# MCU.net
KiCad netlist of a schematic drawn in Altium Designer
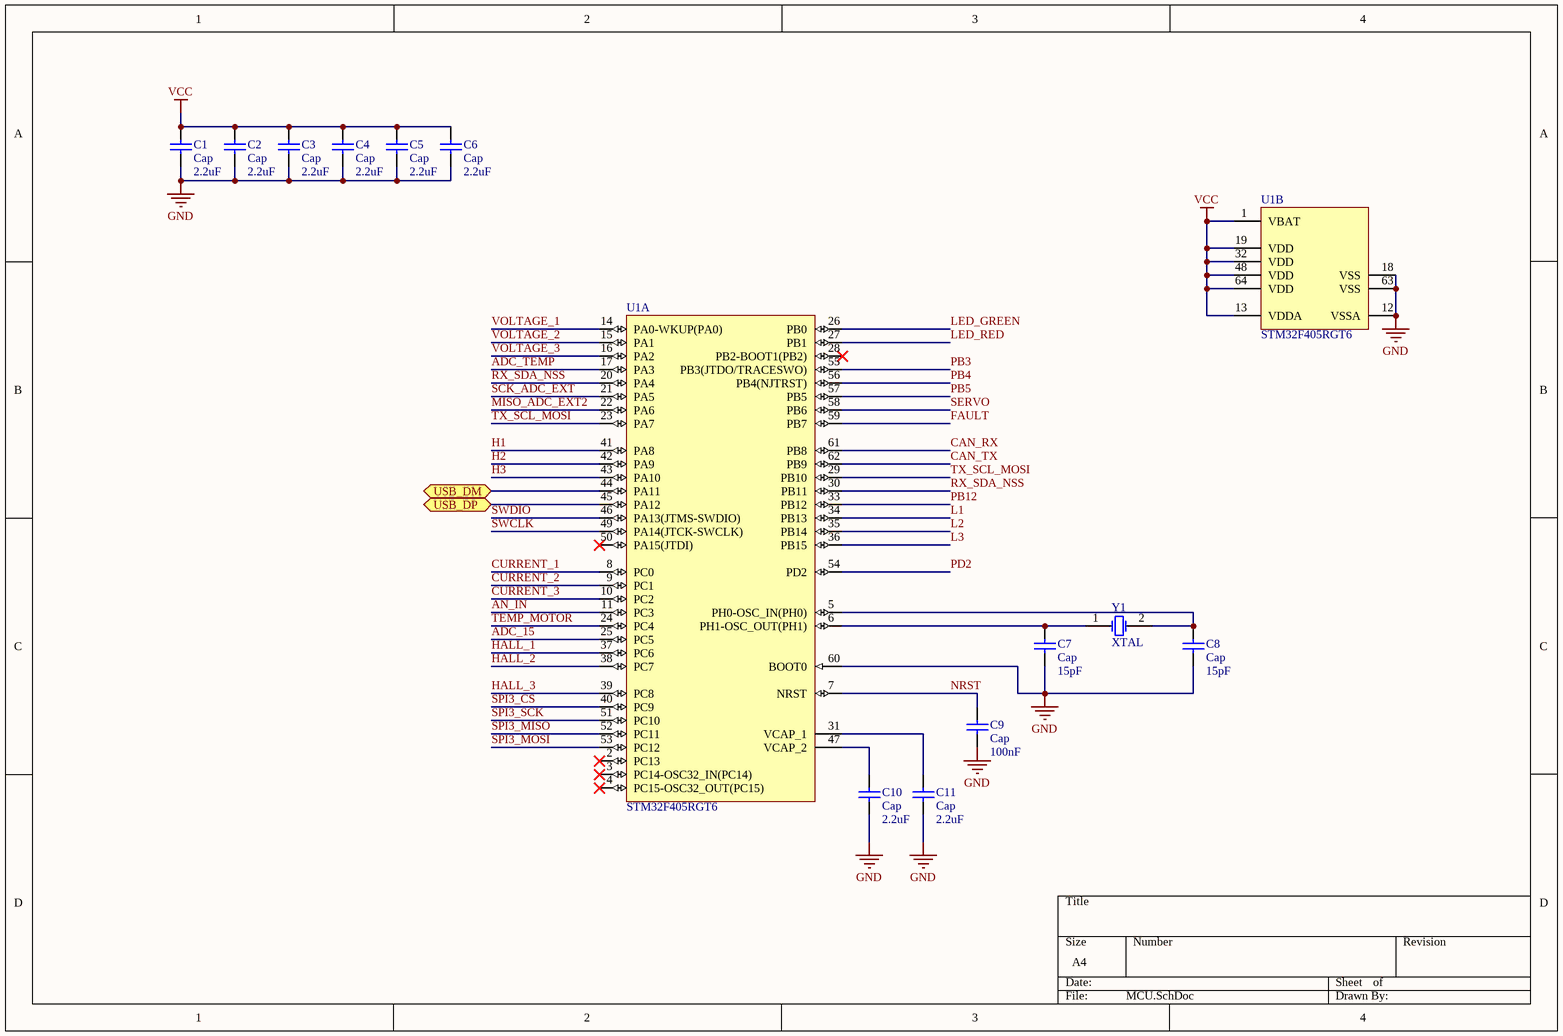
[diagram p0: MCU.SchDoc]

(export (version "E")
  (design (tool "Eeschema 10.0.6"))
  (components
    (comp (ref "C1")
      (value "Cap")
      (footprint "RAD-0.3")
      (description "Capacitor")
      (fields (field (name "ALTIUM_VALUE") "2.2uF") (field (name "PUBLISHER") "Altium Limited"))
      (libsource (lib "Miscellaneous Devices") (part "Cap"))
    )
    (comp (ref "C2")
      (value "Cap")
      (footprint "RAD-0.3")
      (description "Capacitor")
      (fields (field (name "ALTIUM_VALUE") "2.2uF") (field (name "PUBLISHER") "Altium Limited"))
      (libsource (lib "Miscellaneous Devices") (part "Cap"))
    )
    (comp (ref "C3")
      (value "Cap")
      (footprint "RAD-0.3")
      (description "Capacitor")
      (fields (field (name "ALTIUM_VALUE") "2.2uF") (field (name "PUBLISHER") "Altium Limited"))
      (libsource (lib "Miscellaneous Devices") (part "Cap"))
    )
    (comp (ref "C4")
      (value "Cap")
      (footprint "RAD-0.3")
      (description "Capacitor")
      (fields (field (name "ALTIUM_VALUE") "2.2uF") (field (name "PUBLISHER") "Altium Limited"))
      (libsource (lib "Miscellaneous Devices") (part "Cap"))
    )
    (comp (ref "C5")
      (value "Cap")
      (footprint "RAD-0.3")
      (description "Capacitor")
      (fields (field (name "ALTIUM_VALUE") "2.2uF") (field (name "PUBLISHER") "Altium Limited"))
      (libsource (lib "Miscellaneous Devices") (part "Cap"))
    )
    (comp (ref "C6")
      (value "Cap")
      (footprint "RAD-0.3")
      (description "Capacitor")
      (fields (field (name "ALTIUM_VALUE") "2.2uF") (field (name "PUBLISHER") "Altium Limited"))
      (libsource (lib "Miscellaneous Devices") (part "Cap"))
    )
    (comp (ref "C7")
      (value "Cap")
      (footprint "RAD-0.3")
      (description "Capacitor")
      (fields (field (name "ALTIUM_VALUE") "15pF") (field (name "PUBLISHER") "Altium Limited"))
      (libsource (lib "Miscellaneous Devices") (part "Cap"))
    )
    (comp (ref "C8")
      (value "Cap")
      (footprint "RAD-0.3")
      (description "Capacitor")
      (fields (field (name "ALTIUM_VALUE") "15pF") (field (name "PUBLISHER") "Altium Limited"))
      (libsource (lib "Miscellaneous Devices") (part "Cap"))
    )
    (comp (ref "C9")
      (value "Cap")
      (footprint "RAD-0.3")
      (description "Capacitor")
      (fields (field (name "ALTIUM_VALUE") "100nF") (field (name "PUBLISHER") "Altium Limited"))
      (libsource (lib "Miscellaneous Devices") (part "Cap"))
    )
    (comp (ref "C10")
      (value "Cap")
      (footprint "RAD-0.3")
      (description "Capacitor")
      (fields (field (name "ALTIUM_VALUE") "2.2uF") (field (name "PUBLISHER") "Altium Limited"))
      (libsource (lib "Miscellaneous Devices") (part "Cap"))
    )
    (comp (ref "C11")
      (value "Cap")
      (footprint "RAD-0.3")
      (description "Capacitor")
      (fields (field (name "ALTIUM_VALUE") "2.2uF") (field (name "PUBLISHER") "Altium Limited"))
      (libsource (lib "Miscellaneous Devices") (part "Cap"))
    )
    (comp (ref "U1")
      (value "STM32F405RGT6")
      (footprint "STM-LQFP64_M")
      (fields (field (name "MANUFACTURER") "STMicroelectronics"))
      (libsource (lib "Altium Content Vault") (part "MC-ARM-STM32F4X5-SQ64"))
    )
    (comp (ref "Y1")
      (value "XTAL")
      (footprint "R38")
      (description "Crystal Oscillator")
      (fields (field (name "PUBLISHER") "Altium Limited"))
      (libsource (lib "Miscellaneous Devices") (part "XTAL"))
    )
  )
  (nets
    (net (code "1") (name "/ADC_15") (class "Default")
      (node (ref "U1") (pin "25") (pinfunction "PC5_25") (pintype "bidirectional"))
    )
    (net (code "2") (name "/ADC_TEMP") (class "Default")
      (node (ref "U1") (pin "17") (pinfunction "PA3_17") (pintype "bidirectional"))
    )
    (net (code "3") (name "/AN_IN") (class "Default")
      (node (ref "U1") (pin "11") (pinfunction "PC3_11") (pintype "bidirectional"))
    )
    (net (code "4") (name "/CAN_RX") (class "Default")
      (node (ref "U1") (pin "61") (pinfunction "PB8_61") (pintype "bidirectional"))
    )
    (net (code "5") (name "/CAN_TX") (class "Default")
      (node (ref "U1") (pin "62") (pinfunction "PB9_62") (pintype "bidirectional"))
    )
    (net (code "6") (name "/CURRENT_1") (class "Default")
      (node (ref "U1") (pin "8") (pinfunction "PC0_8") (pintype "bidirectional"))
    )
    (net (code "7") (name "/CURRENT_2") (class "Default")
      (node (ref "U1") (pin "9") (pinfunction "PC1_9") (pintype "bidirectional"))
    )
    (net (code "8") (name "/CURRENT_3") (class "Default")
      (node (ref "U1") (pin "10") (pinfunction "PC2_10") (pintype "bidirectional"))
    )
    (net (code "9") (name "/FAULT") (class "Default")
      (node (ref "U1") (pin "59") (pinfunction "PB7_59") (pintype "bidirectional"))
    )
    (net (code "10") (name "/H1") (class "Default")
      (node (ref "U1") (pin "41") (pinfunction "PA8_41") (pintype "bidirectional"))
    )
    (net (code "11") (name "/H2") (class "Default")
      (node (ref "U1") (pin "42") (pinfunction "PA9_42") (pintype "bidirectional"))
    )
    (net (code "12") (name "/H3") (class "Default")
      (node (ref "U1") (pin "43") (pinfunction "PA10_43") (pintype "bidirectional"))
    )
    (net (code "13") (name "/HALL_1") (class "Default")
      (node (ref "U1") (pin "37") (pinfunction "PC6_37") (pintype "bidirectional"))
    )
    (net (code "14") (name "/HALL_2") (class "Default")
      (node (ref "U1") (pin "38") (pinfunction "PC7_38") (pintype "bidirectional"))
    )
    (net (code "15") (name "/HALL_3") (class "Default")
      (node (ref "U1") (pin "39") (pinfunction "PC8_39") (pintype "bidirectional"))
    )
    (net (code "16") (name "/L1") (class "Default")
      (node (ref "U1") (pin "34") (pinfunction "PB13_34") (pintype "bidirectional"))
    )
    (net (code "17") (name "/L2") (class "Default")
      (node (ref "U1") (pin "35") (pinfunction "PB14_35") (pintype "bidirectional"))
    )
    (net (code "18") (name "/L3") (class "Default")
      (node (ref "U1") (pin "36") (pinfunction "PB15_36") (pintype "bidirectional"))
    )
    (net (code "19") (name "/LED_GREEN") (class "Default")
      (node (ref "U1") (pin "26") (pinfunction "PB0_26") (pintype "bidirectional"))
    )
    (net (code "20") (name "/LED_RED") (class "Default")
      (node (ref "U1") (pin "27") (pinfunction "PB1_27") (pintype "bidirectional"))
    )
    (net (code "21") (name "/MISO_ADC_EXT2") (class "Default")
      (node (ref "U1") (pin "22") (pinfunction "PA6_22") (pintype "bidirectional"))
    )
    (net (code "22") (name "/NRST") (class "Default")
      (node (ref "C9") (pin "2") (pinfunction "2_2") (pintype "passive"))
      (node (ref "U1") (pin "7") (pinfunction "NRST_7") (pintype "bidirectional"))
    )
    (net (code "23") (name "/PB3") (class "Default")
      (node (ref "U1") (pin "55") (pinfunction "PB3(JTDO/TRACESWO)_55") (pintype "bidirectional"))
    )
    (net (code "24") (name "/PB4") (class "Default")
      (node (ref "U1") (pin "56") (pinfunction "PB4(NJTRST)_56") (pintype "bidirectional"))
    )
    (net (code "25") (name "/PB5") (class "Default")
      (node (ref "U1") (pin "57") (pinfunction "PB5_57") (pintype "bidirectional"))
    )
    (net (code "26") (name "/PB12") (class "Default")
      (node (ref "U1") (pin "33") (pinfunction "PB12_33") (pintype "bidirectional"))
    )
    (net (code "27") (name "/PD2") (class "Default")
      (node (ref "U1") (pin "54") (pinfunction "PD2_54") (pintype "bidirectional"))
    )
    (net (code "28") (name "/RX_SDA_NSS") (class "Default")
      (node (ref "U1") (pin "20") (pinfunction "PA4_20") (pintype "bidirectional"))
      (node (ref "U1") (pin "30") (pinfunction "PB11_30") (pintype "bidirectional"))
    )
    (net (code "29") (name "/SCK_ADC_EXT") (class "Default")
      (node (ref "U1") (pin "21") (pinfunction "PA5_21") (pintype "bidirectional"))
    )
    (net (code "30") (name "/SERVO") (class "Default")
      (node (ref "U1") (pin "58") (pinfunction "PB6_58") (pintype "bidirectional"))
    )
    (net (code "31") (name "/SPI3_CS") (class "Default")
      (node (ref "U1") (pin "40") (pinfunction "PC9_40") (pintype "bidirectional"))
    )
    (net (code "32") (name "/SPI3_MISO") (class "Default")
      (node (ref "U1") (pin "52") (pinfunction "PC11_52") (pintype "bidirectional"))
    )
    (net (code "33") (name "/SPI3_MOSI") (class "Default")
      (node (ref "U1") (pin "53") (pinfunction "PC12_53") (pintype "bidirectional"))
    )
    (net (code "34") (name "/SPI3_SCK") (class "Default")
      (node (ref "U1") (pin "51") (pinfunction "PC10_51") (pintype "bidirectional"))
    )
    (net (code "35") (name "/SWCLK") (class "Default")
      (node (ref "U1") (pin "49") (pinfunction "PA14(JTCK-SWCLK)_49") (pintype "bidirectional"))
    )
    (net (code "36") (name "/SWDIO") (class "Default")
      (node (ref "U1") (pin "46") (pinfunction "PA13(JTMS-SWDIO)_46") (pintype "bidirectional"))
    )
    (net (code "37") (name "/TEMP_MOTOR") (class "Default")
      (node (ref "U1") (pin "24") (pinfunction "PC4_24") (pintype "bidirectional"))
    )
    (net (code "38") (name "/TX_SCL_MOSI") (class "Default")
      (node (ref "U1") (pin "23") (pinfunction "PA7_23") (pintype "bidirectional"))
      (node (ref "U1") (pin "29") (pinfunction "PB10_29") (pintype "bidirectional"))
    )
    (net (code "39") (name "/USB_DM") (class "Default")
      (node (ref "U1") (pin "44") (pinfunction "PA11_44") (pintype "bidirectional"))
    )
    (net (code "40") (name "/USB_DP") (class "Default")
      (node (ref "U1") (pin "45") (pinfunction "PA12_45") (pintype "bidirectional"))
    )
    (net (code "41") (name "/VOLTAGE_1") (class "Default")
      (node (ref "U1") (pin "14") (pinfunction "PA0-WKUP(PA0)_14") (pintype "bidirectional"))
    )
    (net (code "42") (name "/VOLTAGE_2") (class "Default")
      (node (ref "U1") (pin "15") (pinfunction "PA1_15") (pintype "bidirectional"))
    )
    (net (code "43") (name "/VOLTAGE_3") (class "Default")
      (node (ref "U1") (pin "16") (pinfunction "PA2_16") (pintype "bidirectional"))
    )
    (net (code "44") (name "GND") (class "Default")
      (node (ref "C1") (pin "1") (pinfunction "1_1") (pintype "passive"))
      (node (ref "C10") (pin "1") (pinfunction "1_1") (pintype "passive"))
      (node (ref "C11") (pin "1") (pinfunction "1_1") (pintype "passive"))
      (node (ref "C2") (pin "1") (pinfunction "1_1") (pintype "passive"))
      (node (ref "C3") (pin "1") (pinfunction "1_1") (pintype "passive"))
      (node (ref "C4") (pin "1") (pinfunction "1_1") (pintype "passive"))
      (node (ref "C5") (pin "1") (pinfunction "1_1") (pintype "passive"))
      (node (ref "C6") (pin "1") (pinfunction "1_1") (pintype "passive"))
      (node (ref "C7") (pin "1") (pinfunction "1_1") (pintype "passive"))
      (node (ref "C8") (pin "1") (pinfunction "1_1") (pintype "passive"))
      (node (ref "C9") (pin "1") (pinfunction "1_1") (pintype "passive"))
      (node (ref "U1") (pin "12") (pinfunction "VSSA_12") (pintype "power_in"))
      (node (ref "U1") (pin "18") (pinfunction "VSS_18") (pintype "power_in"))
      (node (ref "U1") (pin "60") (pinfunction "BOOT0_60") (pintype "input"))
      (node (ref "U1") (pin "63") (pinfunction "VSS_63") (pintype "power_in"))
    )
    (net (code "45") (name "Net-(U1A-PH0-OSC_IN(PH0))") (class "Default")
      (node (ref "C8") (pin "2") (pinfunction "2_2") (pintype "passive"))
      (node (ref "U1") (pin "5") (pinfunction "PH0-OSC_IN(PH0)_5") (pintype "bidirectional"))
      (node (ref "Y1") (pin "2") (pinfunction "OSC2_2") (pintype "passive"))
    )
    (net (code "46") (name "Net-(U1A-PH1-OSC_OUT(PH1))") (class "Default")
      (node (ref "C7") (pin "2") (pinfunction "2_2") (pintype "passive"))
      (node (ref "U1") (pin "6") (pinfunction "PH1-OSC_OUT(PH1)_6") (pintype "bidirectional"))
      (node (ref "Y1") (pin "1") (pinfunction "OSC1_1") (pintype "passive"))
    )
    (net (code "47") (name "Net-(U1A-VCAP_1)") (class "Default")
      (node (ref "C11") (pin "2") (pinfunction "2_2") (pintype "passive"))
      (node (ref "U1") (pin "31") (pinfunction "VCAP_1_31") (pintype "power_in"))
    )
    (net (code "48") (name "Net-(U1A-VCAP_2)") (class "Default")
      (node (ref "C10") (pin "2") (pinfunction "2_2") (pintype "passive"))
      (node (ref "U1") (pin "47") (pinfunction "VCAP_2_47") (pintype "power_in"))
    )
    (net (code "49") (name "VCC") (class "Default")
      (node (ref "C1") (pin "2") (pinfunction "2_2") (pintype "passive"))
      (node (ref "C2") (pin "2") (pinfunction "2_2") (pintype "passive"))
      (node (ref "C3") (pin "2") (pinfunction "2_2") (pintype "passive"))
      (node (ref "C4") (pin "2") (pinfunction "2_2") (pintype "passive"))
      (node (ref "C5") (pin "2") (pinfunction "2_2") (pintype "passive"))
      (node (ref "C6") (pin "2") (pinfunction "2_2") (pintype "passive"))
      (node (ref "U1") (pin "1") (pinfunction "VBAT_1") (pintype "power_in"))
      (node (ref "U1") (pin "13") (pinfunction "VDDA_13") (pintype "power_in"))
      (node (ref "U1") (pin "19") (pinfunction "VDD_19") (pintype "power_in"))
      (node (ref "U1") (pin "32") (pinfunction "VDD_32") (pintype "power_in"))
      (node (ref "U1") (pin "48") (pinfunction "VDD_48") (pintype "power_in"))
      (node (ref "U1") (pin "64") (pinfunction "VDD_64") (pintype "power_in"))
    )
    (net (code "50") (name "unconnected-(U1A-PA15(JTDI)-Pad50)") (class "Default")
      (node (ref "U1") (pin "50") (pinfunction "PA15(JTDI)_50") (pintype "bidirectional+no_connect"))
    )
    (net (code "51") (name "unconnected-(U1A-PB2-BOOT1(PB2)-Pad28)") (class "Default")
      (node (ref "U1") (pin "28") (pinfunction "PB2-BOOT1(PB2)_28") (pintype "bidirectional+no_connect"))
    )
    (net (code "52") (name "unconnected-(U1A-PC13-Pad2)") (class "Default")
      (node (ref "U1") (pin "2") (pinfunction "PC13_2") (pintype "bidirectional+no_connect"))
    )
    (net (code "53") (name "unconnected-(U1A-PC14-OSC32_IN(PC14)-Pad3)") (class "Default")
      (node (ref "U1") (pin "3") (pinfunction "PC14-OSC32_IN(PC14)_3") (pintype "bidirectional+no_connect"))
    )
    (net (code "54") (name "unconnected-(U1A-PC15-OSC32_OUT(PC15)-Pad4)") (class "Default")
      (node (ref "U1") (pin "4") (pinfunction "PC15-OSC32_OUT(PC15)_4") (pintype "bidirectional+no_connect"))
    )
  )
)
